# temp-stellwerk-a-2.net
KiCad netlist of a schematic drawn in EAGLE
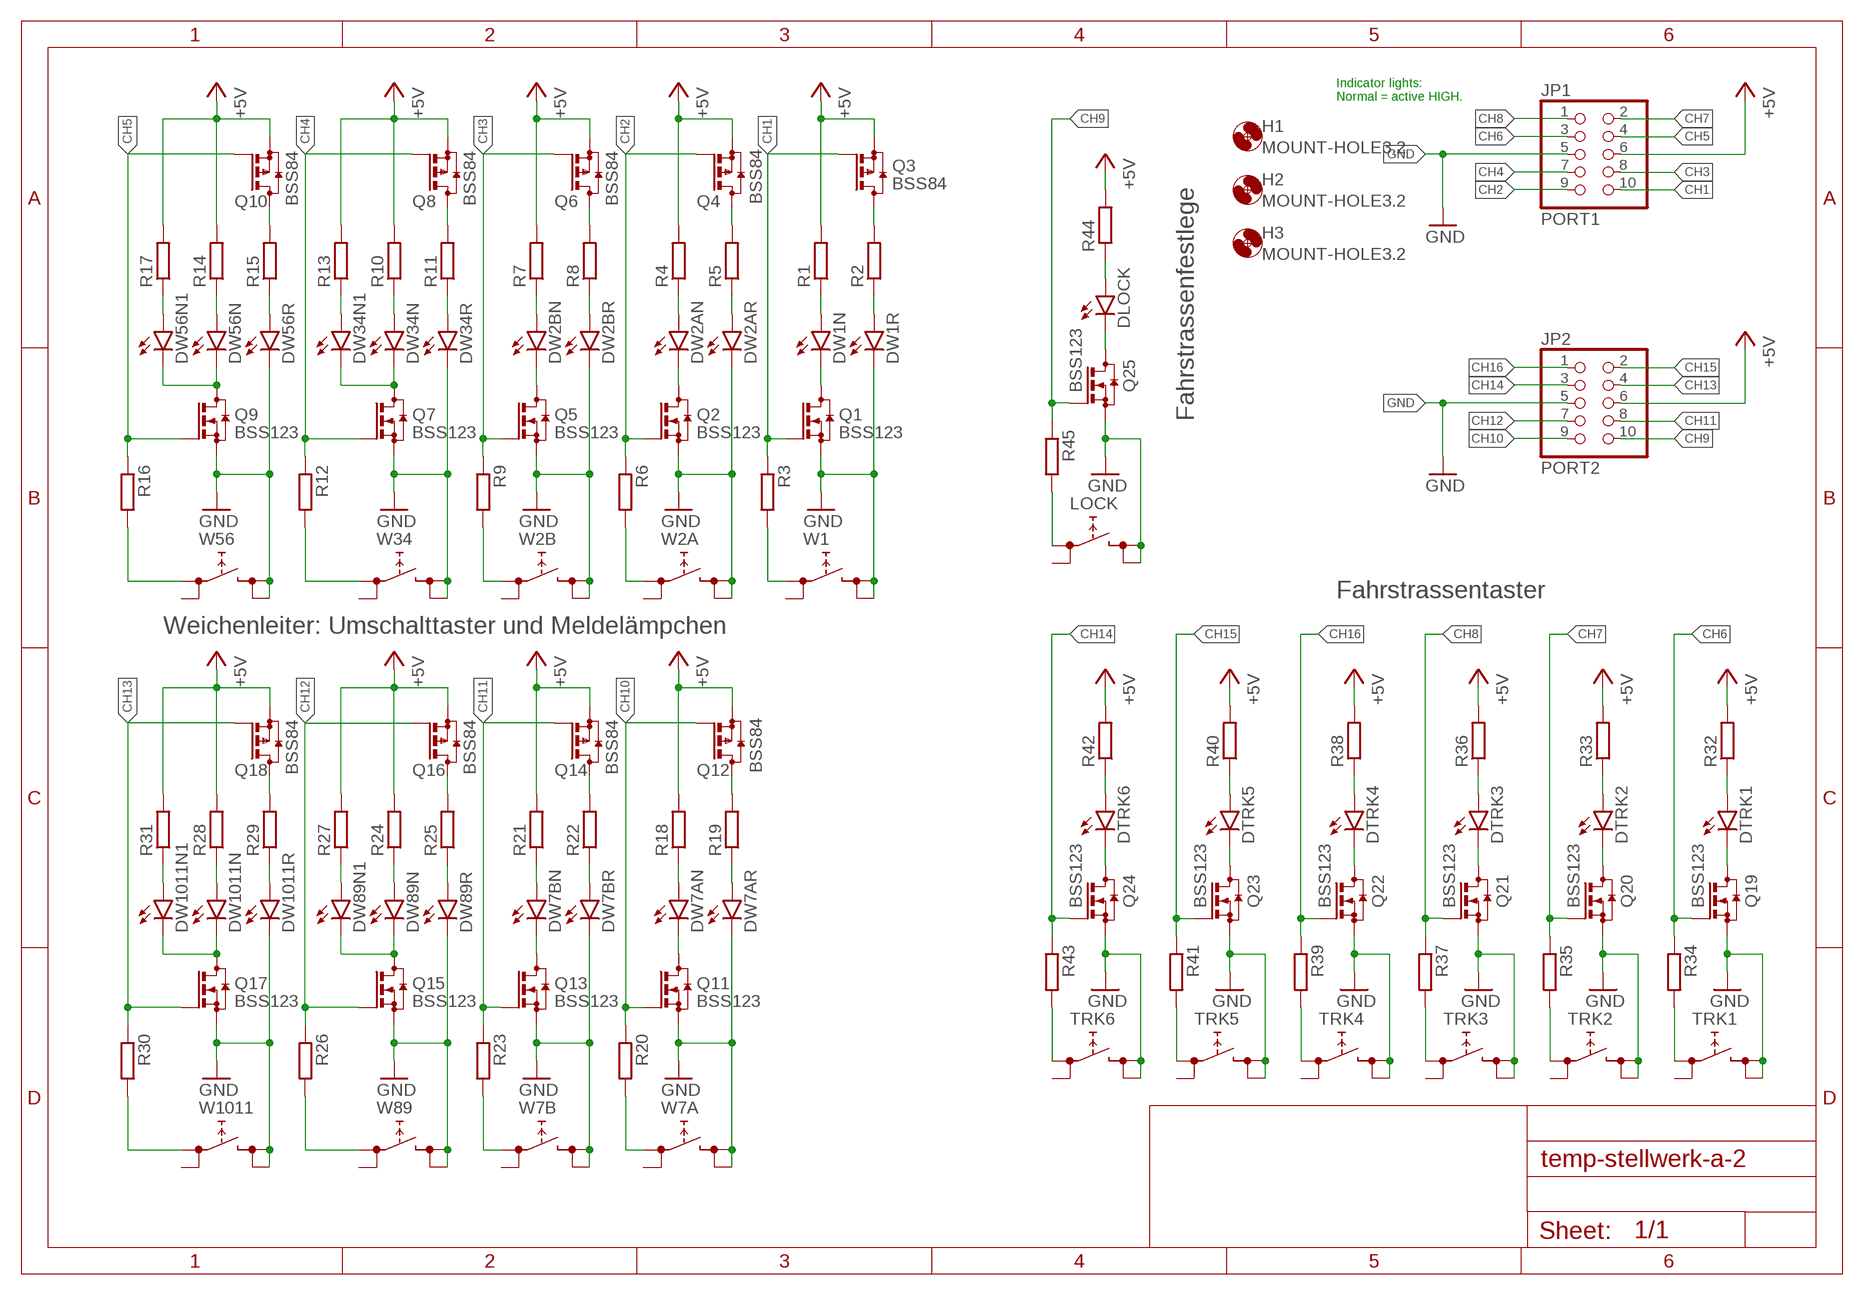
[diagram p0: schematic, sheet 1]

(export (version "E")
  (design (tool "Eeschema 10.0.6"))
  (components
    (comp (ref "DLOCK")
      (value "LEDCHIP-LED0805")
      (footprint "eagle-import:CHIP-LED0805")
      (libsource (lib "eagle-import") (part "LEDCHIP-LED0805"))
    )
    (comp (ref "DTRK1")
      (value "LEDCHIP-LED0805")
      (footprint "eagle-import:CHIP-LED0805")
      (libsource (lib "eagle-import") (part "LEDCHIP-LED0805"))
    )
    (comp (ref "DTRK2")
      (value "LEDCHIP-LED0805")
      (footprint "eagle-import:CHIP-LED0805")
      (libsource (lib "eagle-import") (part "LEDCHIP-LED0805"))
    )
    (comp (ref "DTRK3")
      (value "LEDCHIP-LED0805")
      (footprint "eagle-import:CHIP-LED0805")
      (libsource (lib "eagle-import") (part "LEDCHIP-LED0805"))
    )
    (comp (ref "DTRK4")
      (value "LEDCHIP-LED0805")
      (footprint "eagle-import:CHIP-LED0805")
      (libsource (lib "eagle-import") (part "LEDCHIP-LED0805"))
    )
    (comp (ref "DTRK5")
      (value "LEDCHIP-LED0805")
      (footprint "eagle-import:CHIP-LED0805")
      (libsource (lib "eagle-import") (part "LEDCHIP-LED0805"))
    )
    (comp (ref "DTRK6")
      (value "LEDCHIP-LED0805")
      (footprint "eagle-import:CHIP-LED0805")
      (libsource (lib "eagle-import") (part "LEDCHIP-LED0805"))
    )
    (comp (ref "DW1N")
      (value "LEDCHIP-LED0603")
      (footprint "eagle-import:CHIP-LED0603")
      (libsource (lib "eagle-import") (part "LEDCHIP-LED0603"))
    )
    (comp (ref "DW1R")
      (value "LEDCHIP-LED0603")
      (footprint "eagle-import:CHIP-LED0603")
      (libsource (lib "eagle-import") (part "LEDCHIP-LED0603"))
    )
    (comp (ref "DW2AN")
      (value "LEDCHIP-LED0603")
      (footprint "eagle-import:CHIP-LED0603")
      (libsource (lib "eagle-import") (part "LEDCHIP-LED0603"))
    )
    (comp (ref "DW2AR")
      (value "LEDCHIP-LED0603")
      (footprint "eagle-import:CHIP-LED0603")
      (libsource (lib "eagle-import") (part "LEDCHIP-LED0603"))
    )
    (comp (ref "DW2BN")
      (value "LEDCHIP-LED0805")
      (footprint "eagle-import:CHIP-LED0805")
      (libsource (lib "eagle-import") (part "LEDCHIP-LED0805"))
    )
    (comp (ref "DW2BR")
      (value "LEDCHIP-LED0805")
      (footprint "eagle-import:CHIP-LED0805")
      (libsource (lib "eagle-import") (part "LEDCHIP-LED0805"))
    )
    (comp (ref "DW7AN")
      (value "LEDCHIPLED_0603")
      (footprint "eagle-import:CHIPLED_0603")
      (libsource (lib "eagle-import") (part "LEDCHIPLED_0603"))
    )
    (comp (ref "DW7AR")
      (value "LEDCHIP-LED0603")
      (footprint "eagle-import:CHIP-LED0603")
      (libsource (lib "eagle-import") (part "LEDCHIP-LED0603"))
    )
    (comp (ref "DW7BN")
      (value "LEDCHIP-LED0805")
      (footprint "eagle-import:CHIP-LED0805")
      (libsource (lib "eagle-import") (part "LEDCHIP-LED0805"))
    )
    (comp (ref "DW7BR")
      (value "LEDCHIP-LED0805")
      (footprint "eagle-import:CHIP-LED0805")
      (libsource (lib "eagle-import") (part "LEDCHIP-LED0805"))
    )
    (comp (ref "DW34N")
      (value "LEDCHIP-LED0805")
      (footprint "eagle-import:CHIP-LED0805")
      (libsource (lib "eagle-import") (part "LEDCHIP-LED0805"))
    )
    (comp (ref "DW34N1")
      (value "LEDCHIP-LED0805")
      (footprint "eagle-import:CHIP-LED0805")
      (libsource (lib "eagle-import") (part "LEDCHIP-LED0805"))
    )
    (comp (ref "DW34R")
      (value "LEDCHIP-LED0805")
      (footprint "eagle-import:CHIP-LED0805")
      (libsource (lib "eagle-import") (part "LEDCHIP-LED0805"))
    )
    (comp (ref "DW56N")
      (value "LEDCHIP-LED0805")
      (footprint "eagle-import:CHIP-LED0805")
      (libsource (lib "eagle-import") (part "LEDCHIP-LED0805"))
    )
    (comp (ref "DW56N1")
      (value "LEDCHIP-LED0805")
      (footprint "eagle-import:CHIP-LED0805")
      (libsource (lib "eagle-import") (part "LEDCHIP-LED0805"))
    )
    (comp (ref "DW56R")
      (value "LEDCHIP-LED0805")
      (footprint "eagle-import:CHIP-LED0805")
      (libsource (lib "eagle-import") (part "LEDCHIP-LED0805"))
    )
    (comp (ref "DW89N")
      (value "LEDCHIP-LED0805")
      (footprint "eagle-import:CHIP-LED0805")
      (libsource (lib "eagle-import") (part "LEDCHIP-LED0805"))
    )
    (comp (ref "DW89N1")
      (value "LEDCHIP-LED0805")
      (footprint "eagle-import:CHIP-LED0805")
      (libsource (lib "eagle-import") (part "LEDCHIP-LED0805"))
    )
    (comp (ref "DW89R")
      (value "LEDCHIP-LED0805")
      (footprint "eagle-import:CHIP-LED0805")
      (libsource (lib "eagle-import") (part "LEDCHIP-LED0805"))
    )
    (comp (ref "DW1011N")
      (value "LEDCHIP-LED0805")
      (footprint "eagle-import:CHIP-LED0805")
      (libsource (lib "eagle-import") (part "LEDCHIP-LED0805"))
    )
    (comp (ref "DW1011N1")
      (value "LEDCHIP-LED0805")
      (footprint "eagle-import:CHIP-LED0805")
      (libsource (lib "eagle-import") (part "LEDCHIP-LED0805"))
    )
    (comp (ref "DW1011R")
      (value "LEDCHIP-LED0805")
      (footprint "eagle-import:CHIP-LED0805")
      (libsource (lib "eagle-import") (part "LEDCHIP-LED0805"))
    )
    (comp (ref "H1")
      (value "MOUNT-HOLE3.2")
      (footprint "eagle-import:3,2")
      (libsource (lib "eagle-import") (part "MOUNT-HOLE3.2"))
    )
    (comp (ref "H2")
      (value "MOUNT-HOLE3.2")
      (footprint "eagle-import:3,2")
      (libsource (lib "eagle-import") (part "MOUNT-HOLE3.2"))
    )
    (comp (ref "H3")
      (value "MOUNT-HOLE3.2")
      (footprint "eagle-import:3,2")
      (libsource (lib "eagle-import") (part "MOUNT-HOLE3.2"))
    )
    (comp (ref "JP1")
      (value "PORT1")
      (footprint "eagle-import:CON10M")
      (libsource (lib "eagle-import") (part "PINHD-2X5CN"))
    )
    (comp (ref "JP2")
      (value "PORT2")
      (footprint "eagle-import:CON10M")
      (libsource (lib "eagle-import") (part "PINHD-2X5CN"))
    )
    (comp (ref "LOCK")
      (value "LOCK")
      (footprint "eagle-import:TACTSW-6X6")
      (libsource (lib "eagle-import") (part "TACTSW-6X6S"))
    )
    (comp (ref "Q1")
      (value "BSS123")
      (footprint "eagle-import:SOT23")
      (libsource (lib "eagle-import") (part "BSS123"))
    )
    (comp (ref "Q2")
      (value "BSS123")
      (footprint "eagle-import:SOT23")
      (libsource (lib "eagle-import") (part "BSS123"))
    )
    (comp (ref "Q3")
      (value "BSS84")
      (footprint "eagle-import:SOT23")
      (libsource (lib "eagle-import") (part "BSS84"))
    )
    (comp (ref "Q4")
      (value "BSS84")
      (footprint "eagle-import:SOT23")
      (libsource (lib "eagle-import") (part "BSS84"))
    )
    (comp (ref "Q5")
      (value "BSS123")
      (footprint "eagle-import:SOT23")
      (libsource (lib "eagle-import") (part "BSS123"))
    )
    (comp (ref "Q6")
      (value "BSS84")
      (footprint "eagle-import:SOT23")
      (libsource (lib "eagle-import") (part "BSS84"))
    )
    (comp (ref "Q7")
      (value "BSS123")
      (footprint "eagle-import:SOT23")
      (libsource (lib "eagle-import") (part "BSS123"))
    )
    (comp (ref "Q8")
      (value "BSS84")
      (footprint "eagle-import:SOT23")
      (libsource (lib "eagle-import") (part "BSS84"))
    )
    (comp (ref "Q9")
      (value "BSS123")
      (footprint "eagle-import:SOT23")
      (libsource (lib "eagle-import") (part "BSS123"))
    )
    (comp (ref "Q10")
      (value "BSS84")
      (footprint "eagle-import:SOT23")
      (libsource (lib "eagle-import") (part "BSS84"))
    )
    (comp (ref "Q11")
      (value "BSS123")
      (footprint "eagle-import:SOT23")
      (libsource (lib "eagle-import") (part "BSS123"))
    )
    (comp (ref "Q12")
      (value "BSS84")
      (footprint "eagle-import:SOT23")
      (libsource (lib "eagle-import") (part "BSS84"))
    )
    (comp (ref "Q13")
      (value "BSS123")
      (footprint "eagle-import:SOT23")
      (libsource (lib "eagle-import") (part "BSS123"))
    )
    (comp (ref "Q14")
      (value "BSS84")
      (footprint "eagle-import:SOT23")
      (libsource (lib "eagle-import") (part "BSS84"))
    )
    (comp (ref "Q15")
      (value "BSS123")
      (footprint "eagle-import:SOT23")
      (libsource (lib "eagle-import") (part "BSS123"))
    )
    (comp (ref "Q16")
      (value "BSS84")
      (footprint "eagle-import:SOT23")
      (libsource (lib "eagle-import") (part "BSS84"))
    )
    (comp (ref "Q17")
      (value "BSS123")
      (footprint "eagle-import:SOT23")
      (libsource (lib "eagle-import") (part "BSS123"))
    )
    (comp (ref "Q18")
      (value "BSS84")
      (footprint "eagle-import:SOT23")
      (libsource (lib "eagle-import") (part "BSS84"))
    )
    (comp (ref "Q19")
      (value "BSS123")
      (footprint "eagle-import:SOT23")
      (libsource (lib "eagle-import") (part "BSS123"))
    )
    (comp (ref "Q20")
      (value "BSS123")
      (footprint "eagle-import:SOT23")
      (libsource (lib "eagle-import") (part "BSS123"))
    )
    (comp (ref "Q21")
      (value "BSS123")
      (footprint "eagle-import:SOT23")
      (libsource (lib "eagle-import") (part "BSS123"))
    )
    (comp (ref "Q22")
      (value "BSS123")
      (footprint "eagle-import:SOT23")
      (libsource (lib "eagle-import") (part "BSS123"))
    )
    (comp (ref "Q23")
      (value "BSS123")
      (footprint "eagle-import:SOT23")
      (libsource (lib "eagle-import") (part "BSS123"))
    )
    (comp (ref "Q24")
      (value "BSS123")
      (footprint "eagle-import:SOT23")
      (libsource (lib "eagle-import") (part "BSS123"))
    )
    (comp (ref "Q25")
      (value "BSS123")
      (footprint "eagle-import:SOT23")
      (libsource (lib "eagle-import") (part "BSS123"))
    )
    (comp (ref "R1")
      (value "R-EU_R0805")
      (footprint "eagle-import:R0805")
      (libsource (lib "eagle-import") (part "R-EU_R0805"))
    )
    (comp (ref "R2")
      (value "R-EU_R0805")
      (footprint "eagle-import:R0805")
      (libsource (lib "eagle-import") (part "R-EU_R0805"))
    )
    (comp (ref "R3")
      (value "R-EU_R0805")
      (footprint "eagle-import:R0805")
      (libsource (lib "eagle-import") (part "R-EU_R0805"))
    )
    (comp (ref "R4")
      (value "R-EU_R0805")
      (footprint "eagle-import:R0805")
      (libsource (lib "eagle-import") (part "R-EU_R0805"))
    )
    (comp (ref "R5")
      (value "R-EU_R0805")
      (footprint "eagle-import:R0805")
      (libsource (lib "eagle-import") (part "R-EU_R0805"))
    )
    (comp (ref "R6")
      (value "R-EU_R0805")
      (footprint "eagle-import:R0805")
      (libsource (lib "eagle-import") (part "R-EU_R0805"))
    )
    (comp (ref "R7")
      (value "R-EU_R0805")
      (footprint "eagle-import:R0805")
      (libsource (lib "eagle-import") (part "R-EU_R0805"))
    )
    (comp (ref "R8")
      (value "R-EU_R0805")
      (footprint "eagle-import:R0805")
      (libsource (lib "eagle-import") (part "R-EU_R0805"))
    )
    (comp (ref "R9")
      (value "R-EU_R0805")
      (footprint "eagle-import:R0805")
      (libsource (lib "eagle-import") (part "R-EU_R0805"))
    )
    (comp (ref "R10")
      (value "R-EU_R0805")
      (footprint "eagle-import:R0805")
      (libsource (lib "eagle-import") (part "R-EU_R0805"))
    )
    (comp (ref "R11")
      (value "R-EU_R0805")
      (footprint "eagle-import:R0805")
      (libsource (lib "eagle-import") (part "R-EU_R0805"))
    )
    (comp (ref "R12")
      (value "R-EU_R0805")
      (footprint "eagle-import:R0805")
      (libsource (lib "eagle-import") (part "R-EU_R0805"))
    )
    (comp (ref "R13")
      (value "R-EU_R0805")
      (footprint "eagle-import:R0805")
      (libsource (lib "eagle-import") (part "R-EU_R0805"))
    )
    (comp (ref "R14")
      (value "R-EU_R0805")
      (footprint "eagle-import:R0805")
      (libsource (lib "eagle-import") (part "R-EU_R0805"))
    )
    (comp (ref "R15")
      (value "R-EU_R0805")
      (footprint "eagle-import:R0805")
      (libsource (lib "eagle-import") (part "R-EU_R0805"))
    )
    (comp (ref "R16")
      (value "R-EU_R0805")
      (footprint "eagle-import:R0805")
      (libsource (lib "eagle-import") (part "R-EU_R0805"))
    )
    (comp (ref "R17")
      (value "R-EU_R0805")
      (footprint "eagle-import:R0805")
      (libsource (lib "eagle-import") (part "R-EU_R0805"))
    )
    (comp (ref "R18")
      (value "R-EU_R0805")
      (footprint "eagle-import:R0805")
      (libsource (lib "eagle-import") (part "R-EU_R0805"))
    )
    (comp (ref "R19")
      (value "R-EU_R0805")
      (footprint "eagle-import:R0805")
      (libsource (lib "eagle-import") (part "R-EU_R0805"))
    )
    (comp (ref "R20")
      (value "R-EU_R0805")
      (footprint "eagle-import:R0805")
      (libsource (lib "eagle-import") (part "R-EU_R0805"))
    )
    (comp (ref "R21")
      (value "R-EU_R0805")
      (footprint "eagle-import:R0805")
      (libsource (lib "eagle-import") (part "R-EU_R0805"))
    )
    (comp (ref "R22")
      (value "R-EU_R0805")
      (footprint "eagle-import:R0805")
      (libsource (lib "eagle-import") (part "R-EU_R0805"))
    )
    (comp (ref "R23")
      (value "R-EU_R0805")
      (footprint "eagle-import:R0805")
      (libsource (lib "eagle-import") (part "R-EU_R0805"))
    )
    (comp (ref "R24")
      (value "R-EU_R0805")
      (footprint "eagle-import:R0805")
      (libsource (lib "eagle-import") (part "R-EU_R0805"))
    )
    (comp (ref "R25")
      (value "R-EU_R0805")
      (footprint "eagle-import:R0805")
      (libsource (lib "eagle-import") (part "R-EU_R0805"))
    )
    (comp (ref "R26")
      (value "R-EU_R0805")
      (footprint "eagle-import:R0805")
      (libsource (lib "eagle-import") (part "R-EU_R0805"))
    )
    (comp (ref "R27")
      (value "R-EU_R0805")
      (footprint "eagle-import:R0805")
      (libsource (lib "eagle-import") (part "R-EU_R0805"))
    )
    (comp (ref "R28")
      (value "R-EU_R0805")
      (footprint "eagle-import:R0805")
      (libsource (lib "eagle-import") (part "R-EU_R0805"))
    )
    (comp (ref "R29")
      (value "R-EU_R0805")
      (footprint "eagle-import:R0805")
      (libsource (lib "eagle-import") (part "R-EU_R0805"))
    )
    (comp (ref "R30")
      (value "R-EU_R0805")
      (footprint "eagle-import:R0805")
      (libsource (lib "eagle-import") (part "R-EU_R0805"))
    )
    (comp (ref "R31")
      (value "R-EU_R0805")
      (footprint "eagle-import:R0805")
      (libsource (lib "eagle-import") (part "R-EU_R0805"))
    )
    (comp (ref "R32")
      (value "R-EU_R0805")
      (footprint "eagle-import:R0805")
      (libsource (lib "eagle-import") (part "R-EU_R0805"))
    )
    (comp (ref "R33")
      (value "R-EU_R0805")
      (footprint "eagle-import:R0805")
      (libsource (lib "eagle-import") (part "R-EU_R0805"))
    )
    (comp (ref "R34")
      (value "R-EU_R0805")
      (footprint "eagle-import:R0805")
      (libsource (lib "eagle-import") (part "R-EU_R0805"))
    )
    (comp (ref "R35")
      (value "R-EU_R0805")
      (footprint "eagle-import:R0805")
      (libsource (lib "eagle-import") (part "R-EU_R0805"))
    )
    (comp (ref "R36")
      (value "R-EU_R0805")
      (footprint "eagle-import:R0805")
      (libsource (lib "eagle-import") (part "R-EU_R0805"))
    )
    (comp (ref "R37")
      (value "R-EU_R0805")
      (footprint "eagle-import:R0805")
      (libsource (lib "eagle-import") (part "R-EU_R0805"))
    )
    (comp (ref "R38")
      (value "R-EU_R0805")
      (footprint "eagle-import:R0805")
      (libsource (lib "eagle-import") (part "R-EU_R0805"))
    )
    (comp (ref "R39")
      (value "R-EU_R0805")
      (footprint "eagle-import:R0805")
      (libsource (lib "eagle-import") (part "R-EU_R0805"))
    )
    (comp (ref "R40")
      (value "R-EU_R0805")
      (footprint "eagle-import:R0805")
      (libsource (lib "eagle-import") (part "R-EU_R0805"))
    )
    (comp (ref "R41")
      (value "R-EU_R0805")
      (footprint "eagle-import:R0805")
      (libsource (lib "eagle-import") (part "R-EU_R0805"))
    )
    (comp (ref "R42")
      (value "R-EU_R0805")
      (footprint "eagle-import:R0805")
      (libsource (lib "eagle-import") (part "R-EU_R0805"))
    )
    (comp (ref "R43")
      (value "R-EU_R0805")
      (footprint "eagle-import:R0805")
      (libsource (lib "eagle-import") (part "R-EU_R0805"))
    )
    (comp (ref "R44")
      (value "R-EU_R0805")
      (footprint "eagle-import:R0805")
      (libsource (lib "eagle-import") (part "R-EU_R0805"))
    )
    (comp (ref "R45")
      (value "R-EU_R0805")
      (footprint "eagle-import:R0805")
      (libsource (lib "eagle-import") (part "R-EU_R0805"))
    )
    (comp (ref "TRK1")
      (value "TACTSW-6X6S")
      (footprint "eagle-import:TACTSW-6X6")
      (libsource (lib "eagle-import") (part "TACTSW-6X6S"))
    )
    (comp (ref "TRK2")
      (value "TACTSW-6X6S")
      (footprint "eagle-import:TACTSW-6X6")
      (libsource (lib "eagle-import") (part "TACTSW-6X6S"))
    )
    (comp (ref "TRK3")
      (value "TACTSW-6X6S")
      (footprint "eagle-import:TACTSW-6X6")
      (libsource (lib "eagle-import") (part "TACTSW-6X6S"))
    )
    (comp (ref "TRK4")
      (value "TACTSW-6X6S")
      (footprint "eagle-import:TACTSW-6X6")
      (libsource (lib "eagle-import") (part "TACTSW-6X6S"))
    )
    (comp (ref "TRK5")
      (value "TACTSW-6X6S")
      (footprint "eagle-import:TACTSW-6X6")
      (libsource (lib "eagle-import") (part "TACTSW-6X6S"))
    )
    (comp (ref "TRK6")
      (value "TACTSW-6X6S")
      (footprint "eagle-import:TACTSW-6X6")
      (libsource (lib "eagle-import") (part "TACTSW-6X6S"))
    )
    (comp (ref "W1")
      (value "W1")
      (footprint "eagle-import:TACTSW-6X6")
      (libsource (lib "eagle-import") (part "TACTSW-6X6S"))
    )
    (comp (ref "W2A")
      (value "TACTSW-6X6S")
      (footprint "eagle-import:TACTSW-6X6")
      (libsource (lib "eagle-import") (part "TACTSW-6X6S"))
    )
    (comp (ref "W2B")
      (value "TACTSW-6X6S")
      (footprint "eagle-import:TACTSW-6X6")
      (libsource (lib "eagle-import") (part "TACTSW-6X6S"))
    )
    (comp (ref "W7A")
      (value "TACTSW-6X6S")
      (footprint "eagle-import:TACTSW-6X6")
      (libsource (lib "eagle-import") (part "TACTSW-6X6S"))
    )
    (comp (ref "W7B")
      (value "TACTSW-6X6S")
      (footprint "eagle-import:TACTSW-6X6")
      (libsource (lib "eagle-import") (part "TACTSW-6X6S"))
    )
    (comp (ref "W34")
      (value "XOVER")
      (footprint "eagle-import:TACTSW-6X6")
      (libsource (lib "eagle-import") (part "TACTSW-6X6S"))
    )
    (comp (ref "W56")
      (value "XOVER")
      (footprint "eagle-import:TACTSW-6X6")
      (libsource (lib "eagle-import") (part "TACTSW-6X6S"))
    )
    (comp (ref "W89")
      (value "XOVER")
      (footprint "eagle-import:TACTSW-6X6")
      (libsource (lib "eagle-import") (part "TACTSW-6X6S"))
    )
    (comp (ref "W1011")
      (value "XOVER")
      (footprint "eagle-import:TACTSW-6X6")
      (libsource (lib "eagle-import") (part "TACTSW-6X6S"))
    )
  )
  (nets
    (net (code "1") (name "+5V") (class "Default")
      (node (ref "JP1") (pin "6") (pinfunction "6_6") (pintype "passive"))
      (node (ref "JP2") (pin "6") (pinfunction "6_6") (pintype "passive"))
      (node (ref "Q10") (pin "2") (pinfunction "S_2") (pintype "passive"))
      (node (ref "Q12") (pin "2") (pinfunction "S_2") (pintype "passive"))
      (node (ref "Q14") (pin "2") (pinfunction "S_2") (pintype "passive"))
      (node (ref "Q16") (pin "2") (pinfunction "S_2") (pintype "passive"))
      (node (ref "Q18") (pin "2") (pinfunction "S_2") (pintype "passive"))
      (node (ref "Q3") (pin "2") (pinfunction "S_2") (pintype "passive"))
      (node (ref "Q4") (pin "2") (pinfunction "S_2") (pintype "passive"))
      (node (ref "Q6") (pin "2") (pinfunction "S_2") (pintype "passive"))
      (node (ref "Q8") (pin "2") (pinfunction "S_2") (pintype "passive"))
      (node (ref "R1") (pin "2") (pinfunction "2_2") (pintype "passive"))
      (node (ref "R10") (pin "2") (pinfunction "2_2") (pintype "passive"))
      (node (ref "R13") (pin "2") (pinfunction "2_2") (pintype "passive"))
      (node (ref "R14") (pin "2") (pinfunction "2_2") (pintype "passive"))
      (node (ref "R17") (pin "2") (pinfunction "2_2") (pintype "passive"))
      (node (ref "R18") (pin "2") (pinfunction "2_2") (pintype "passive"))
      (node (ref "R21") (pin "2") (pinfunction "2_2") (pintype "passive"))
      (node (ref "R24") (pin "2") (pinfunction "2_2") (pintype "passive"))
      (node (ref "R27") (pin "2") (pinfunction "2_2") (pintype "passive"))
      (node (ref "R28") (pin "2") (pinfunction "2_2") (pintype "passive"))
      (node (ref "R31") (pin "2") (pinfunction "2_2") (pintype "passive"))
      (node (ref "R32") (pin "2") (pinfunction "2_2") (pintype "passive"))
      (node (ref "R33") (pin "2") (pinfunction "2_2") (pintype "passive"))
      (node (ref "R36") (pin "2") (pinfunction "2_2") (pintype "passive"))
      (node (ref "R38") (pin "2") (pinfunction "2_2") (pintype "passive"))
      (node (ref "R4") (pin "2") (pinfunction "2_2") (pintype "passive"))
      (node (ref "R40") (pin "2") (pinfunction "2_2") (pintype "passive"))
      (node (ref "R42") (pin "2") (pinfunction "2_2") (pintype "passive"))
      (node (ref "R44") (pin "2") (pinfunction "2_2") (pintype "passive"))
      (node (ref "R7") (pin "2") (pinfunction "2_2") (pintype "passive"))
    )
    (net (code "2") (name "CH1") (class "Default")
      (node (ref "JP1") (pin "10") (pinfunction "10_10") (pintype "passive"))
      (node (ref "Q1") (pin "1") (pinfunction "G_1") (pintype "passive"))
      (node (ref "Q3") (pin "1") (pinfunction "G_1") (pintype "passive"))
      (node (ref "R3") (pin "1") (pinfunction "1_1") (pintype "passive"))
    )
    (net (code "3") (name "CH2") (class "Default")
      (node (ref "JP1") (pin "9") (pinfunction "9_9") (pintype "passive"))
      (node (ref "Q2") (pin "1") (pinfunction "G_1") (pintype "passive"))
      (node (ref "Q4") (pin "1") (pinfunction "G_1") (pintype "passive"))
      (node (ref "R6") (pin "1") (pinfunction "1_1") (pintype "passive"))
    )
    (net (code "4") (name "CH3") (class "Default")
      (node (ref "JP1") (pin "8") (pinfunction "8_8") (pintype "passive"))
      (node (ref "Q5") (pin "1") (pinfunction "G_1") (pintype "passive"))
      (node (ref "Q6") (pin "1") (pinfunction "G_1") (pintype "passive"))
      (node (ref "R9") (pin "1") (pinfunction "1_1") (pintype "passive"))
    )
    (net (code "5") (name "CH4") (class "Default")
      (node (ref "JP1") (pin "7") (pinfunction "7_7") (pintype "passive"))
      (node (ref "Q7") (pin "1") (pinfunction "G_1") (pintype "passive"))
      (node (ref "Q8") (pin "1") (pinfunction "G_1") (pintype "passive"))
      (node (ref "R12") (pin "1") (pinfunction "1_1") (pintype "passive"))
    )
    (net (code "6") (name "CH5") (class "Default")
      (node (ref "JP1") (pin "4") (pinfunction "4_4") (pintype "passive"))
      (node (ref "Q10") (pin "1") (pinfunction "G_1") (pintype "passive"))
      (node (ref "Q9") (pin "1") (pinfunction "G_1") (pintype "passive"))
      (node (ref "R16") (pin "1") (pinfunction "1_1") (pintype "passive"))
    )
    (net (code "7") (name "CH6") (class "Default")
      (node (ref "JP1") (pin "3") (pinfunction "3_3") (pintype "passive"))
      (node (ref "Q19") (pin "1") (pinfunction "G_1") (pintype "passive"))
      (node (ref "R34") (pin "1") (pinfunction "1_1") (pintype "passive"))
    )
    (net (code "8") (name "CH7") (class "Default")
      (node (ref "JP1") (pin "2") (pinfunction "2_2") (pintype "passive"))
      (node (ref "Q20") (pin "1") (pinfunction "G_1") (pintype "passive"))
      (node (ref "R35") (pin "1") (pinfunction "1_1") (pintype "passive"))
    )
    (net (code "9") (name "CH8") (class "Default")
      (node (ref "JP1") (pin "1") (pinfunction "1_1") (pintype "passive"))
      (node (ref "Q21") (pin "1") (pinfunction "G_1") (pintype "passive"))
      (node (ref "R37") (pin "1") (pinfunction "1_1") (pintype "passive"))
    )
    (net (code "10") (name "CH9") (class "Default")
      (node (ref "JP2") (pin "10") (pinfunction "10_10") (pintype "passive"))
      (node (ref "Q25") (pin "1") (pinfunction "G_1") (pintype "passive"))
      (node (ref "R45") (pin "1") (pinfunction "1_1") (pintype "passive"))
    )
    (net (code "11") (name "CH10") (class "Default")
      (node (ref "JP2") (pin "9") (pinfunction "9_9") (pintype "passive"))
      (node (ref "Q11") (pin "1") (pinfunction "G_1") (pintype "passive"))
      (node (ref "Q12") (pin "1") (pinfunction "G_1") (pintype "passive"))
      (node (ref "R20") (pin "1") (pinfunction "1_1") (pintype "passive"))
    )
    (net (code "12") (name "CH11") (class "Default")
      (node (ref "JP2") (pin "8") (pinfunction "8_8") (pintype "passive"))
      (node (ref "Q13") (pin "1") (pinfunction "G_1") (pintype "passive"))
      (node (ref "Q14") (pin "1") (pinfunction "G_1") (pintype "passive"))
      (node (ref "R23") (pin "1") (pinfunction "1_1") (pintype "passive"))
    )
    (net (code "13") (name "CH12") (class "Default")
      (node (ref "JP2") (pin "7") (pinfunction "7_7") (pintype "passive"))
      (node (ref "Q15") (pin "1") (pinfunction "G_1") (pintype "passive"))
      (node (ref "Q16") (pin "1") (pinfunction "G_1") (pintype "passive"))
      (node (ref "R26") (pin "1") (pinfunction "1_1") (pintype "passive"))
    )
    (net (code "14") (name "CH13") (class "Default")
      (node (ref "JP2") (pin "4") (pinfunction "4_4") (pintype "passive"))
      (node (ref "Q17") (pin "1") (pinfunction "G_1") (pintype "passive"))
      (node (ref "Q18") (pin "1") (pinfunction "G_1") (pintype "passive"))
      (node (ref "R30") (pin "1") (pinfunction "1_1") (pintype "passive"))
    )
    (net (code "15") (name "CH14") (class "Default")
      (node (ref "JP2") (pin "3") (pinfunction "3_3") (pintype "passive"))
      (node (ref "Q24") (pin "1") (pinfunction "G_1") (pintype "passive"))
      (node (ref "R43") (pin "1") (pinfunction "1_1") (pintype "passive"))
    )
    (net (code "16") (name "CH15") (class "Default")
      (node (ref "JP2") (pin "2") (pinfunction "2_2") (pintype "passive"))
      (node (ref "Q23") (pin "1") (pinfunction "G_1") (pintype "passive"))
      (node (ref "R41") (pin "1") (pinfunction "1_1") (pintype "passive"))
    )
    (net (code "17") (name "CH16") (class "Default")
      (node (ref "JP2") (pin "1") (pinfunction "1_1") (pintype "passive"))
      (node (ref "Q22") (pin "1") (pinfunction "G_1") (pintype "passive"))
      (node (ref "R39") (pin "1") (pinfunction "1_1") (pintype "passive"))
    )
    (net (code "18") (name "GND") (class "Default")
      (node (ref "DW1011R") (pin "C") (pinfunction "C_C") (pintype "passive"))
      (node (ref "DW1R") (pin "C") (pinfunction "C_C") (pintype "passive"))
      (node (ref "DW2AR") (pin "C") (pinfunction "C_C") (pintype "passive"))
      (node (ref "DW2BR") (pin "C") (pinfunction "C_C") (pintype "passive"))
      (node (ref "DW34R") (pin "C") (pinfunction "C_C") (pintype "passive"))
      (node (ref "DW56R") (pin "C") (pinfunction "C_C") (pintype "passive"))
      (node (ref "DW7AR") (pin "C") (pinfunction "C_C") (pintype "passive"))
      (node (ref "DW7BR") (pin "C") (pinfunction "C_C") (pintype "passive"))
      (node (ref "DW89R") (pin "C") (pinfunction "C_C") (pintype "passive"))
      (node (ref "JP1") (pin "5") (pinfunction "5_5") (pintype "passive"))
      (node (ref "JP2") (pin "5") (pinfunction "5_5") (pintype "passive"))
      (node (ref "LOCK") (pin "3") (pinfunction "2.1_3") (pintype "passive"))
      (node (ref "LOCK") (pin "4") (pinfunction "2.2_4") (pintype "passive"))
      (node (ref "Q1") (pin "2") (pinfunction "S_2") (pintype "passive"))
      (node (ref "Q11") (pin "2") (pinfunction "S_2") (pintype "passive"))
      (node (ref "Q13") (pin "2") (pinfunction "S_2") (pintype "passive"))
      (node (ref "Q15") (pin "2") (pinfunction "S_2") (pintype "passive"))
      (node (ref "Q17") (pin "2") (pinfunction "S_2") (pintype "passive"))
      (node (ref "Q19") (pin "2") (pinfunction "S_2") (pintype "passive"))
      (node (ref "Q2") (pin "2") (pinfunction "S_2") (pintype "passive"))
      (node (ref "Q20") (pin "2") (pinfunction "S_2") (pintype "passive"))
      (node (ref "Q21") (pin "2") (pinfunction "S_2") (pintype "passive"))
      (node (ref "Q22") (pin "2") (pinfunction "S_2") (pintype "passive"))
      (node (ref "Q23") (pin "2") (pinfunction "S_2") (pintype "passive"))
      (node (ref "Q24") (pin "2") (pinfunction "S_2") (pintype "passive"))
      (node (ref "Q25") (pin "2") (pinfunction "S_2") (pintype "passive"))
      (node (ref "Q5") (pin "2") (pinfunction "S_2") (pintype "passive"))
      (node (ref "Q7") (pin "2") (pinfunction "S_2") (pintype "passive"))
      (node (ref "Q9") (pin "2") (pinfunction "S_2") (pintype "passive"))
      (node (ref "TRK1") (pin "3") (pinfunction "2.1_3") (pintype "passive"))
      (node (ref "TRK1") (pin "4") (pinfunction "2.2_4") (pintype "passive"))
      (node (ref "TRK2") (pin "3") (pinfunction "2.1_3") (pintype "passive"))
      (node (ref "TRK2") (pin "4") (pinfunction "2.2_4") (pintype "passive"))
      (node (ref "TRK3") (pin "3") (pinfunction "2.1_3") (pintype "passive"))
      (node (ref "TRK3") (pin "4") (pinfunction "2.2_4") (pintype "passive"))
      (node (ref "TRK4") (pin "3") (pinfunction "2.1_3") (pintype "passive"))
      (node (ref "TRK4") (pin "4") (pinfunction "2.2_4") (pintype "passive"))
      (node (ref "TRK5") (pin "3") (pinfunction "2.1_3") (pintype "passive"))
      (node (ref "TRK5") (pin "4") (pinfunction "2.2_4") (pintype "passive"))
      (node (ref "TRK6") (pin "3") (pinfunction "2.1_3") (pintype "passive"))
      (node (ref "TRK6") (pin "4") (pinfunction "2.2_4") (pintype "passive"))
      (node (ref "W1") (pin "3") (pinfunction "2.1_3") (pintype "passive"))
      (node (ref "W1") (pin "4") (pinfunction "2.2_4") (pintype "passive"))
      (node (ref "W1011") (pin "3") (pinfunction "2.1_3") (pintype "passive"))
      (node (ref "W1011") (pin "4") (pinfunction "2.2_4") (pintype "passive"))
      (node (ref "W2A") (pin "3") (pinfunction "2.1_3") (pintype "passive"))
      (node (ref "W2A") (pin "4") (pinfunction "2.2_4") (pintype "passive"))
      (node (ref "W2B") (pin "3") (pinfunction "2.1_3") (pintype "passive"))
      (node (ref "W2B") (pin "4") (pinfunction "2.2_4") (pintype "passive"))
      (node (ref "W34") (pin "3") (pinfunction "2.1_3") (pintype "passive"))
      (node (ref "W34") (pin "4") (pinfunction "2.2_4") (pintype "passive"))
      (node (ref "W56") (pin "3") (pinfunction "2.1_3") (pintype "passive"))
      (node (ref "W56") (pin "4") (pinfunction "2.2_4") (pintype "passive"))
      (node (ref "W7A") (pin "3") (pinfunction "2.1_3") (pintype "passive"))
      (node (ref "W7A") (pin "4") (pinfunction "2.2_4") (pintype "passive"))
      (node (ref "W7B") (pin "3") (pinfunction "2.1_3") (pintype "passive"))
      (node (ref "W7B") (pin "4") (pinfunction "2.2_4") (pintype "passive"))
      (node (ref "W89") (pin "3") (pinfunction "2.1_3") (pintype "passive"))
      (node (ref "W89") (pin "4") (pinfunction "2.2_4") (pintype "passive"))
    )
    (net (code "19") (name "Net-(DLOCK-PadA)") (class "Default")
      (node (ref "DLOCK") (pin "A") (pinfunction "A_A") (pintype "passive"))
      (node (ref "R44") (pin "1") (pinfunction "1_1") (pintype "passive"))
    )
    (net (code "20") (name "Net-(DTRK1-PadA)") (class "Default")
      (node (ref "DTRK1") (pin "A") (pinfunction "A_A") (pintype "passive"))
      (node (ref "R32") (pin "1") (pinfunction "1_1") (pintype "passive"))
    )
    (net (code "21") (name "Net-(DTRK2-PadA)") (class "Default")
      (node (ref "DTRK2") (pin "A") (pinfunction "A_A") (pintype "passive"))
      (node (ref "R33") (pin "1") (pinfunction "1_1") (pintype "passive"))
    )
    (net (code "22") (name "Net-(DTRK3-PadA)") (class "Default")
      (node (ref "DTRK3") (pin "A") (pinfunction "A_A") (pintype "passive"))
      (node (ref "R36") (pin "1") (pinfunction "1_1") (pintype "passive"))
    )
    (net (code "23") (name "Net-(DTRK4-PadA)") (class "Default")
      (node (ref "DTRK4") (pin "A") (pinfunction "A_A") (pintype "passive"))
      (node (ref "R38") (pin "1") (pinfunction "1_1") (pintype "passive"))
    )
    (net (code "24") (name "Net-(DTRK5-PadA)") (class "Default")
      (node (ref "DTRK5") (pin "A") (pinfunction "A_A") (pintype "passive"))
      (node (ref "R40") (pin "1") (pinfunction "1_1") (pintype "passive"))
    )
    (net (code "25") (name "Net-(DTRK6-PadA)") (class "Default")
      (node (ref "DTRK6") (pin "A") (pinfunction "A_A") (pintype "passive"))
      (node (ref "R42") (pin "1") (pinfunction "1_1") (pintype "passive"))
    )
    (net (code "26") (name "Net-(DW1N-PadA)") (class "Default")
      (node (ref "DW1N") (pin "A") (pinfunction "A_A") (pintype "passive"))
      (node (ref "R1") (pin "1") (pinfunction "1_1") (pintype "passive"))
    )
    (net (code "27") (name "Net-(DW1R-PadA)") (class "Default")
      (node (ref "DW1R") (pin "A") (pinfunction "A_A") (pintype "passive"))
      (node (ref "R2") (pin "1") (pinfunction "1_1") (pintype "passive"))
    )
    (net (code "28") (name "Net-(DW2AN-PadA)") (class "Default")
      (node (ref "DW2AN") (pin "A") (pinfunction "A_A") (pintype "passive"))
      (node (ref "R4") (pin "1") (pinfunction "1_1") (pintype "passive"))
    )
    (net (code "29") (name "Net-(DW2AR-PadA)") (class "Default")
      (node (ref "DW2AR") (pin "A") (pinfunction "A_A") (pintype "passive"))
      (node (ref "R5") (pin "1") (pinfunction "1_1") (pintype "passive"))
    )
    (net (code "30") (name "Net-(DW2BN-PadA)") (class "Default")
      (node (ref "DW2BN") (pin "A") (pinfunction "A_A") (pintype "passive"))
      (node (ref "R7") (pin "1") (pinfunction "1_1") (pintype "passive"))
    )
    (net (code "31") (name "Net-(DW2BR-PadA)") (class "Default")
      (node (ref "DW2BR") (pin "A") (pinfunction "A_A") (pintype "passive"))
      (node (ref "R8") (pin "1") (pinfunction "1_1") (pintype "passive"))
    )
    (net (code "32") (name "Net-(DW7AN-PadA)") (class "Default")
      (node (ref "DW7AN") (pin "A") (pinfunction "A_A") (pintype "passive"))
      (node (ref "R18") (pin "1") (pinfunction "1_1") (pintype "passive"))
    )
    (net (code "33") (name "Net-(DW7AR-PadA)") (class "Default")
      (node (ref "DW7AR") (pin "A") (pinfunction "A_A") (pintype "passive"))
      (node (ref "R19") (pin "1") (pinfunction "1_1") (pintype "passive"))
    )
    (net (code "34") (name "Net-(DW7BN-PadA)") (class "Default")
      (node (ref "DW7BN") (pin "A") (pinfunction "A_A") (pintype "passive"))
      (node (ref "R21") (pin "1") (pinfunction "1_1") (pintype "passive"))
    )
    (net (code "35") (name "Net-(DW7BR-PadA)") (class "Default")
      (node (ref "DW7BR") (pin "A") (pinfunction "A_A") (pintype "passive"))
      (node (ref "R22") (pin "1") (pinfunction "1_1") (pintype "passive"))
    )
    (net (code "36") (name "Net-(DW34N-PadA)") (class "Default")
      (node (ref "DW34N") (pin "A") (pinfunction "A_A") (pintype "passive"))
      (node (ref "R10") (pin "1") (pinfunction "1_1") (pintype "passive"))
    )
    (net (code "37") (name "Net-(DW34N1-PadA)") (class "Default")
      (node (ref "DW34N1") (pin "A") (pinfunction "A_A") (pintype "passive"))
      (node (ref "R13") (pin "1") (pinfunction "1_1") (pintype "passive"))
    )
    (net (code "38") (name "Net-(DW34R-PadA)") (class "Default")
      (node (ref "DW34R") (pin "A") (pinfunction "A_A") (pintype "passive"))
      (node (ref "R11") (pin "1") (pinfunction "1_1") (pintype "passive"))
    )
    (net (code "39") (name "Net-(DW56N-PadA)") (class "Default")
      (node (ref "DW56N") (pin "A") (pinfunction "A_A") (pintype "passive"))
      (node (ref "R14") (pin "1") (pinfunction "1_1") (pintype "passive"))
    )
    (net (code "40") (name "Net-(DW56N1-PadA)") (class "Default")
      (node (ref "DW56N1") (pin "A") (pinfunction "A_A") (pintype "passive"))
      (node (ref "R17") (pin "1") (pinfunction "1_1") (pintype "passive"))
    )
    (net (code "41") (name "Net-(DW56R-PadA)") (class "Default")
      (node (ref "DW56R") (pin "A") (pinfunction "A_A") (pintype "passive"))
      (node (ref "R15") (pin "1") (pinfunction "1_1") (pintype "passive"))
    )
    (net (code "42") (name "Net-(DW89N-PadA)") (class "Default")
      (node (ref "DW89N") (pin "A") (pinfunction "A_A") (pintype "passive"))
      (node (ref "R24") (pin "1") (pinfunction "1_1") (pintype "passive"))
    )
    (net (code "43") (name "Net-(DW89N1-PadA)") (class "Default")
      (node (ref "DW89N1") (pin "A") (pinfunction "A_A") (pintype "passive"))
      (node (ref "R27") (pin "1") (pinfunction "1_1") (pintype "passive"))
    )
    (net (code "44") (name "Net-(DW89R-PadA)") (class "Default")
      (node (ref "DW89R") (pin "A") (pinfunction "A_A") (pintype "passive"))
      (node (ref "R25") (pin "1") (pinfunction "1_1") (pintype "passive"))
    )
    (net (code "45") (name "Net-(DW1011N-PadA)") (class "Default")
      (node (ref "DW1011N") (pin "A") (pinfunction "A_A") (pintype "passive"))
      (node (ref "R28") (pin "1") (pinfunction "1_1") (pintype "passive"))
    )
    (net (code "46") (name "Net-(DW1011N1-PadA)") (class "Default")
      (node (ref "DW1011N1") (pin "A") (pinfunction "A_A") (pintype "passive"))
      (node (ref "R31") (pin "1") (pinfunction "1_1") (pintype "passive"))
    )
    (net (code "47") (name "Net-(DW1011R-PadA)") (class "Default")
      (node (ref "DW1011R") (pin "A") (pinfunction "A_A") (pintype "passive"))
      (node (ref "R29") (pin "1") (pinfunction "1_1") (pintype "passive"))
    )
    (net (code "48") (name "Net-(LOCK-1.1)") (class "Default")
      (node (ref "LOCK") (pin "1") (pinfunction "1.1_1") (pintype "passive"))
      (node (ref "R45") (pin "2") (pinfunction "2_2") (pintype "passive"))
    )
    (net (code "49") (name "Net-(Q1-D)") (class "Default")
      (node (ref "DW1N") (pin "C") (pinfunction "C_C") (pintype "passive"))
      (node (ref "Q1") (pin "3") (pinfunction "D_3") (pintype "passive"))
    )
    (net (code "50") (name "Net-(Q2-D)") (class "Default")
      (node (ref "DW2AN") (pin "C") (pinfunction "C_C") (pintype "passive"))
      (node (ref "Q2") (pin "3") (pinfunction "D_3") (pintype "passive"))
    )
    (net (code "51") (name "Net-(Q3-D)") (class "Default")
      (node (ref "Q3") (pin "3") (pinfunction "D_3") (pintype "passive"))
      (node (ref "R2") (pin "2") (pinfunction "2_2") (pintype "passive"))
    )
    (net (code "52") (name "Net-(Q4-D)") (class "Default")
      (node (ref "Q4") (pin "3") (pinfunction "D_3") (pintype "passive"))
      (node (ref "R5") (pin "2") (pinfunction "2_2") (pintype "passive"))
    )
    (net (code "53") (name "Net-(Q5-D)") (class "Default")
      (node (ref "DW2BN") (pin "C") (pinfunction "C_C") (pintype "passive"))
      (node (ref "Q5") (pin "3") (pinfunction "D_3") (pintype "passive"))
    )
    (net (code "54") (name "Net-(Q6-D)") (class "Default")
      (node (ref "Q6") (pin "3") (pinfunction "D_3") (pintype "passive"))
      (node (ref "R8") (pin "2") (pinfunction "2_2") (pintype "passive"))
    )
    (net (code "55") (name "Net-(Q7-D)") (class "Default")
      (node (ref "DW34N") (pin "C") (pinfunction "C_C") (pintype "passive"))
      (node (ref "DW34N1") (pin "C") (pinfunction "C_C") (pintype "passive"))
      (node (ref "Q7") (pin "3") (pinfunction "D_3") (pintype "passive"))
    )
    (net (code "56") (name "Net-(Q8-D)") (class "Default")
      (node (ref "Q8") (pin "3") (pinfunction "D_3") (pintype "passive"))
      (node (ref "R11") (pin "2") (pinfunction "2_2") (pintype "passive"))
    )
    (net (code "57") (name "Net-(Q9-D)") (class "Default")
      (node (ref "DW56N") (pin "C") (pinfunction "C_C") (pintype "passive"))
      (node (ref "DW56N1") (pin "C") (pinfunction "C_C") (pintype "passive"))
      (node (ref "Q9") (pin "3") (pinfunction "D_3") (pintype "passive"))
    )
    (net (code "58") (name "Net-(Q10-D)") (class "Default")
      (node (ref "Q10") (pin "3") (pinfunction "D_3") (pintype "passive"))
      (node (ref "R15") (pin "2") (pinfunction "2_2") (pintype "passive"))
    )
    (net (code "59") (name "Net-(Q11-D)") (class "Default")
      (node (ref "DW7AN") (pin "C") (pinfunction "C_C") (pintype "passive"))
      (node (ref "Q11") (pin "3") (pinfunction "D_3") (pintype "passive"))
    )
    (net (code "60") (name "Net-(Q12-D)") (class "Default")
      (node (ref "Q12") (pin "3") (pinfunction "D_3") (pintype "passive"))
      (node (ref "R19") (pin "2") (pinfunction "2_2") (pintype "passive"))
    )
    (net (code "61") (name "Net-(Q13-D)") (class "Default")
      (node (ref "DW7BN") (pin "C") (pinfunction "C_C") (pintype "passive"))
      (node (ref "Q13") (pin "3") (pinfunction "D_3") (pintype "passive"))
    )
    (net (code "62") (name "Net-(Q14-D)") (class "Default")
      (node (ref "Q14") (pin "3") (pinfunction "D_3") (pintype "passive"))
      (node (ref "R22") (pin "2") (pinfunction "2_2") (pintype "passive"))
    )
    (net (code "63") (name "Net-(Q15-D)") (class "Default")
      (node (ref "DW89N") (pin "C") (pinfunction "C_C") (pintype "passive"))
      (node (ref "DW89N1") (pin "C") (pinfunction "C_C") (pintype "passive"))
      (node (ref "Q15") (pin "3") (pinfunction "D_3") (pintype "passive"))
    )
    (net (code "64") (name "Net-(Q16-D)") (class "Default")
      (node (ref "Q16") (pin "3") (pinfunction "D_3") (pintype "passive"))
      (node (ref "R25") (pin "2") (pinfunction "2_2") (pintype "passive"))
    )
    (net (code "65") (name "Net-(Q17-D)") (class "Default")
      (node (ref "DW1011N") (pin "C") (pinfunction "C_C") (pintype "passive"))
      (node (ref "DW1011N1") (pin "C") (pinfunction "C_C") (pintype "passive"))
      (node (ref "Q17") (pin "3") (pinfunction "D_3") (pintype "passive"))
    )
    (net (code "66") (name "Net-(Q18-D)") (class "Default")
      (node (ref "Q18") (pin "3") (pinfunction "D_3") (pintype "passive"))
      (node (ref "R29") (pin "2") (pinfunction "2_2") (pintype "passive"))
    )
    (net (code "67") (name "Net-(Q19-D)") (class "Default")
      (node (ref "DTRK1") (pin "C") (pinfunction "C_C") (pintype "passive"))
      (node (ref "Q19") (pin "3") (pinfunction "D_3") (pintype "passive"))
    )
    (net (code "68") (name "Net-(Q20-D)") (class "Default")
      (node (ref "DTRK2") (pin "C") (pinfunction "C_C") (pintype "passive"))
      (node (ref "Q20") (pin "3") (pinfunction "D_3") (pintype "passive"))
    )
    (net (code "69") (name "Net-(Q21-D)") (class "Default")
      (node (ref "DTRK3") (pin "C") (pinfunction "C_C") (pintype "passive"))
      (node (ref "Q21") (pin "3") (pinfunction "D_3") (pintype "passive"))
    )
    (net (code "70") (name "Net-(Q22-D)") (class "Default")
      (node (ref "DTRK4") (pin "C") (pinfunction "C_C") (pintype "passive"))
      (node (ref "Q22") (pin "3") (pinfunction "D_3") (pintype "passive"))
    )
    (net (code "71") (name "Net-(Q23-D)") (class "Default")
      (node (ref "DTRK5") (pin "C") (pinfunction "C_C") (pintype "passive"))
      (node (ref "Q23") (pin "3") (pinfunction "D_3") (pintype "passive"))
    )
    (net (code "72") (name "Net-(Q24-D)") (class "Default")
      (node (ref "DTRK6") (pin "C") (pinfunction "C_C") (pintype "passive"))
      (node (ref "Q24") (pin "3") (pinfunction "D_3") (pintype "passive"))
    )
    (net (code "73") (name "Net-(Q25-D)") (class "Default")
      (node (ref "DLOCK") (pin "C") (pinfunction "C_C") (pintype "passive"))
      (node (ref "Q25") (pin "3") (pinfunction "D_3") (pintype "passive"))
    )
    (net (code "74") (name "Net-(TRK1-1.1)") (class "Default")
      (node (ref "R34") (pin "2") (pinfunction "2_2") (pintype "passive"))
      (node (ref "TRK1") (pin "1") (pinfunction "1.1_1") (pintype "passive"))
    )
    (net (code "75") (name "Net-(TRK2-1.1)") (class "Default")
      (node (ref "R35") (pin "2") (pinfunction "2_2") (pintype "passive"))
      (node (ref "TRK2") (pin "1") (pinfunction "1.1_1") (pintype "passive"))
    )
    (net (code "76") (name "Net-(TRK3-1.1)") (class "Default")
      (node (ref "R37") (pin "2") (pinfunction "2_2") (pintype "passive"))
      (node (ref "TRK3") (pin "1") (pinfunction "1.1_1") (pintype "passive"))
    )
    (net (code "77") (name "Net-(TRK4-1.1)") (class "Default")
      (node (ref "R39") (pin "2") (pinfunction "2_2") (pintype "passive"))
      (node (ref "TRK4") (pin "1") (pinfunction "1.1_1") (pintype "passive"))
    )
    (net (code "78") (name "Net-(TRK5-1.1)") (class "Default")
      (node (ref "R41") (pin "2") (pinfunction "2_2") (pintype "passive"))
      (node (ref "TRK5") (pin "1") (pinfunction "1.1_1") (pintype "passive"))
    )
    (net (code "79") (name "Net-(TRK6-1.1)") (class "Default")
      (node (ref "R43") (pin "2") (pinfunction "2_2") (pintype "passive"))
      (node (ref "TRK6") (pin "1") (pinfunction "1.1_1") (pintype "passive"))
    )
    (net (code "80") (name "Net-(W1-1.1)") (class "Default")
      (node (ref "R3") (pin "2") (pinfunction "2_2") (pintype "passive"))
      (node (ref "W1") (pin "1") (pinfunction "1.1_1") (pintype "passive"))
    )
    (net (code "81") (name "Net-(W2A-1.1)") (class "Default")
      (node (ref "R6") (pin "2") (pinfunction "2_2") (pintype "passive"))
      (node (ref "W2A") (pin "1") (pinfunction "1.1_1") (pintype "passive"))
    )
    (net (code "82") (name "Net-(W2B-1.1)") (class "Default")
      (node (ref "R9") (pin "2") (pinfunction "2_2") (pintype "passive"))
      (node (ref "W2B") (pin "1") (pinfunction "1.1_1") (pintype "passive"))
    )
    (net (code "83") (name "Net-(W7A-1.1)") (class "Default")
      (node (ref "R20") (pin "2") (pinfunction "2_2") (pintype "passive"))
      (node (ref "W7A") (pin "1") (pinfunction "1.1_1") (pintype "passive"))
    )
    (net (code "84") (name "Net-(W7B-1.1)") (class "Default")
      (node (ref "R23") (pin "2") (pinfunction "2_2") (pintype "passive"))
      (node (ref "W7B") (pin "1") (pinfunction "1.1_1") (pintype "passive"))
    )
    (net (code "85") (name "Net-(W34-1.1)") (class "Default")
      (node (ref "R12") (pin "2") (pinfunction "2_2") (pintype "passive"))
      (node (ref "W34") (pin "1") (pinfunction "1.1_1") (pintype "passive"))
    )
    (net (code "86") (name "Net-(W56-1.1)") (class "Default")
      (node (ref "R16") (pin "2") (pinfunction "2_2") (pintype "passive"))
      (node (ref "W56") (pin "1") (pinfunction "1.1_1") (pintype "passive"))
    )
    (net (code "87") (name "Net-(W89-1.1)") (class "Default")
      (node (ref "R26") (pin "2") (pinfunction "2_2") (pintype "passive"))
      (node (ref "W89") (pin "1") (pinfunction "1.1_1") (pintype "passive"))
    )
    (net (code "88") (name "Net-(W1011-1.1)") (class "Default")
      (node (ref "R30") (pin "2") (pinfunction "2_2") (pintype "passive"))
      (node (ref "W1011") (pin "1") (pinfunction "1.1_1") (pintype "passive"))
    )
    (net (code "89") (name "unconnected-(LOCK-1.2-Pad2)") (class "Default")
      (node (ref "LOCK") (pin "2") (pinfunction "1.2_2") (pintype "passive"))
    )
    (net (code "90") (name "unconnected-(TRK1-1.2-Pad2)") (class "Default")
      (node (ref "TRK1") (pin "2") (pinfunction "1.2_2") (pintype "passive"))
    )
    (net (code "91") (name "unconnected-(TRK2-1.2-Pad2)") (class "Default")
      (node (ref "TRK2") (pin "2") (pinfunction "1.2_2") (pintype "passive"))
    )
    (net (code "92") (name "unconnected-(TRK3-1.2-Pad2)") (class "Default")
      (node (ref "TRK3") (pin "2") (pinfunction "1.2_2") (pintype "passive"))
    )
    (net (code "93") (name "unconnected-(TRK4-1.2-Pad2)") (class "Default")
      (node (ref "TRK4") (pin "2") (pinfunction "1.2_2") (pintype "passive"))
    )
    (net (code "94") (name "unconnected-(TRK5-1.2-Pad2)") (class "Default")
      (node (ref "TRK5") (pin "2") (pinfunction "1.2_2") (pintype "passive"))
    )
    (net (code "95") (name "unconnected-(TRK6-1.2-Pad2)") (class "Default")
      (node (ref "TRK6") (pin "2") (pinfunction "1.2_2") (pintype "passive"))
    )
    (net (code "96") (name "unconnected-(W1-1.2-Pad2)") (class "Default")
      (node (ref "W1") (pin "2") (pinfunction "1.2_2") (pintype "passive"))
    )
    (net (code "97") (name "unconnected-(W2A-1.2-Pad2)") (class "Default")
      (node (ref "W2A") (pin "2") (pinfunction "1.2_2") (pintype "passive"))
    )
    (net (code "98") (name "unconnected-(W2B-1.2-Pad2)") (class "Default")
      (node (ref "W2B") (pin "2") (pinfunction "1.2_2") (pintype "passive"))
    )
    (net (code "99") (name "unconnected-(W7A-1.2-Pad2)") (class "Default")
      (node (ref "W7A") (pin "2") (pinfunction "1.2_2") (pintype "passive"))
    )
    (net (code "100") (name "unconnected-(W7B-1.2-Pad2)") (class "Default")
      (node (ref "W7B") (pin "2") (pinfunction "1.2_2") (pintype "passive"))
    )
    (net (code "101") (name "unconnected-(W34-1.2-Pad2)") (class "Default")
      (node (ref "W34") (pin "2") (pinfunction "1.2_2") (pintype "passive"))
    )
    (net (code "102") (name "unconnected-(W56-1.2-Pad2)") (class "Default")
      (node (ref "W56") (pin "2") (pinfunction "1.2_2") (pintype "passive"))
    )
    (net (code "103") (name "unconnected-(W89-1.2-Pad2)") (class "Default")
      (node (ref "W89") (pin "2") (pinfunction "1.2_2") (pintype "passive"))
    )
    (net (code "104") (name "unconnected-(W1011-1.2-Pad2)") (class "Default")
      (node (ref "W1011") (pin "2") (pinfunction "1.2_2") (pintype "passive"))
    )
  )
)
